# NU-Smarticles_old.net
KiCad netlist of a schematic drawn in EAGLE
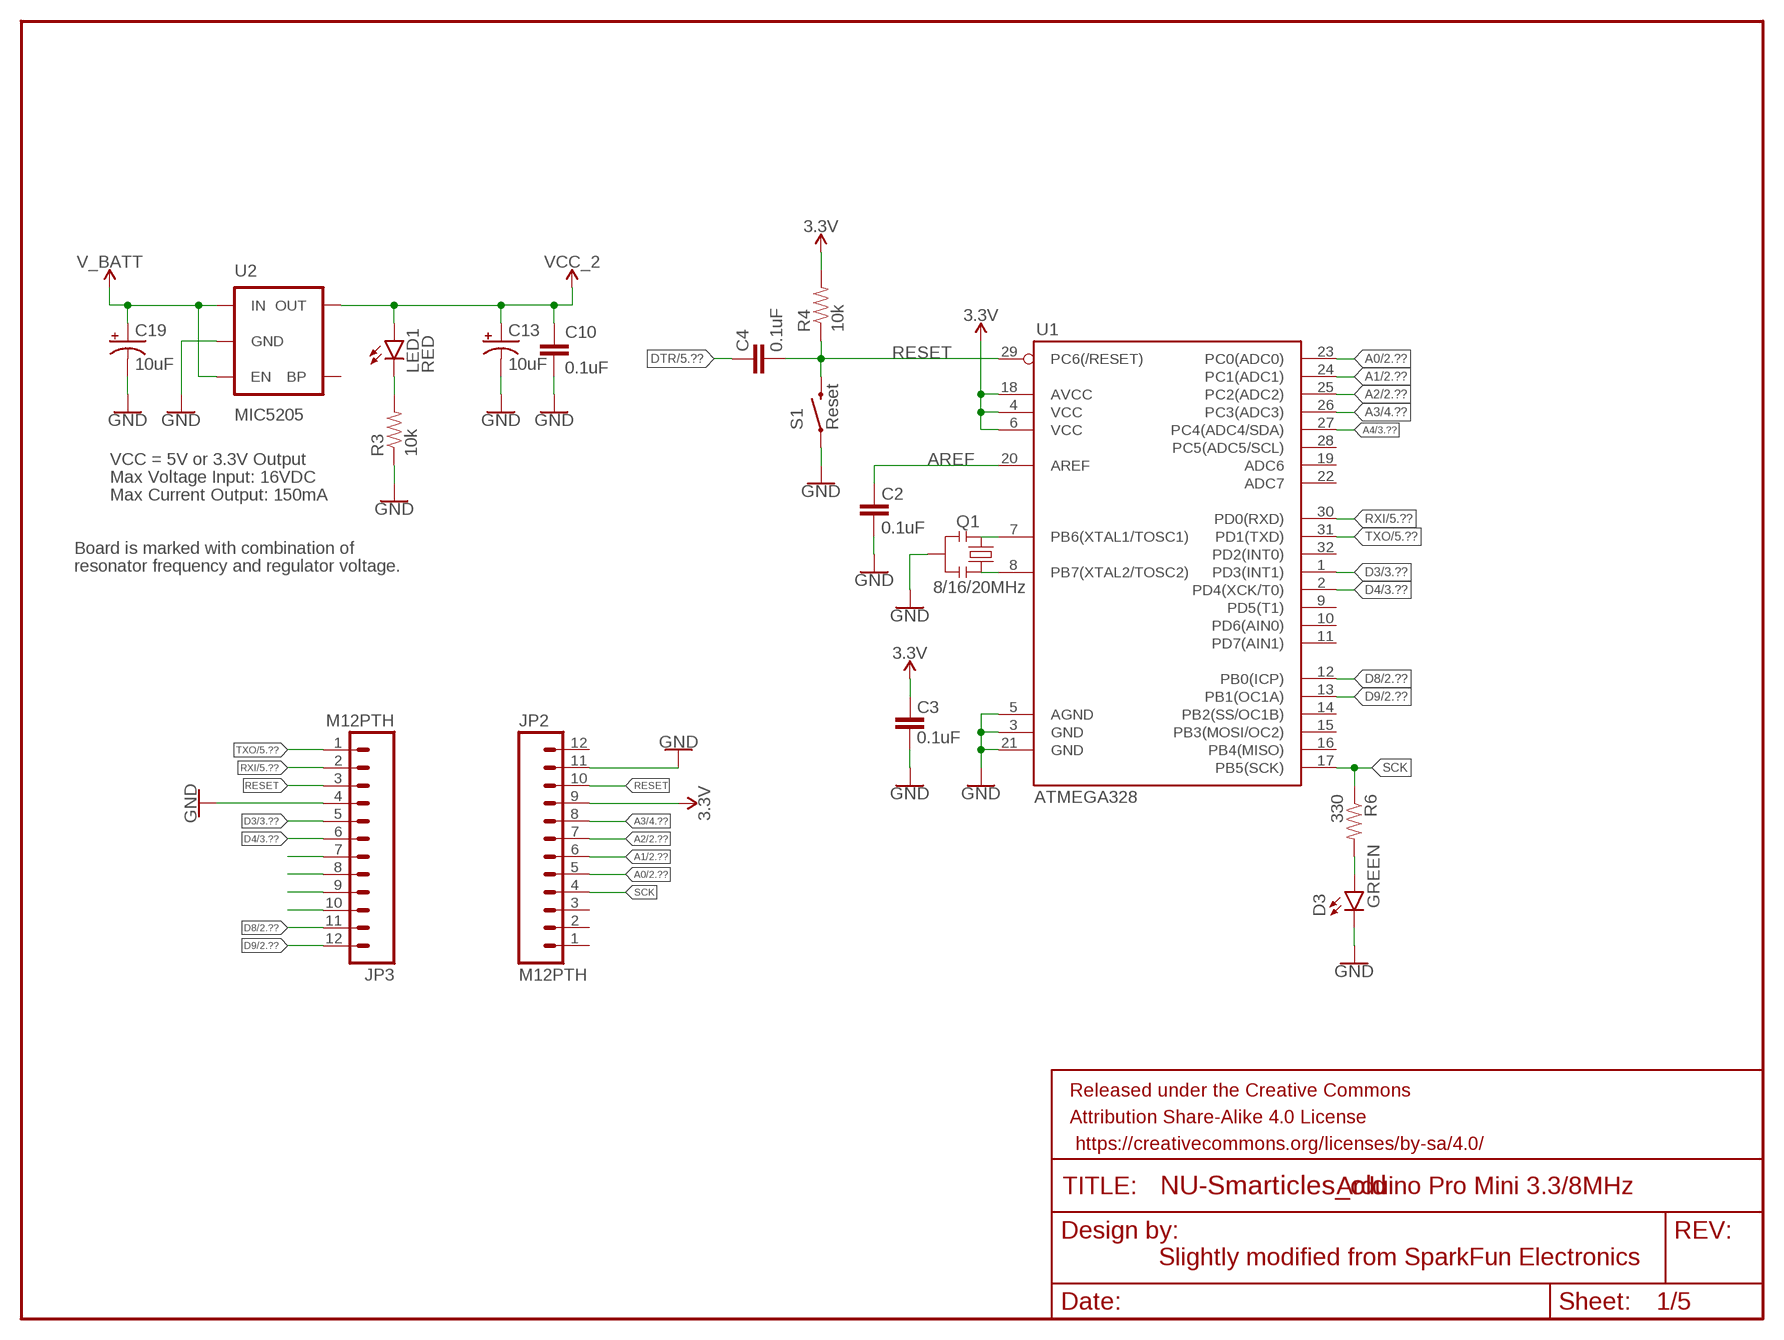
[diagram p0: schematic, sheet 1]
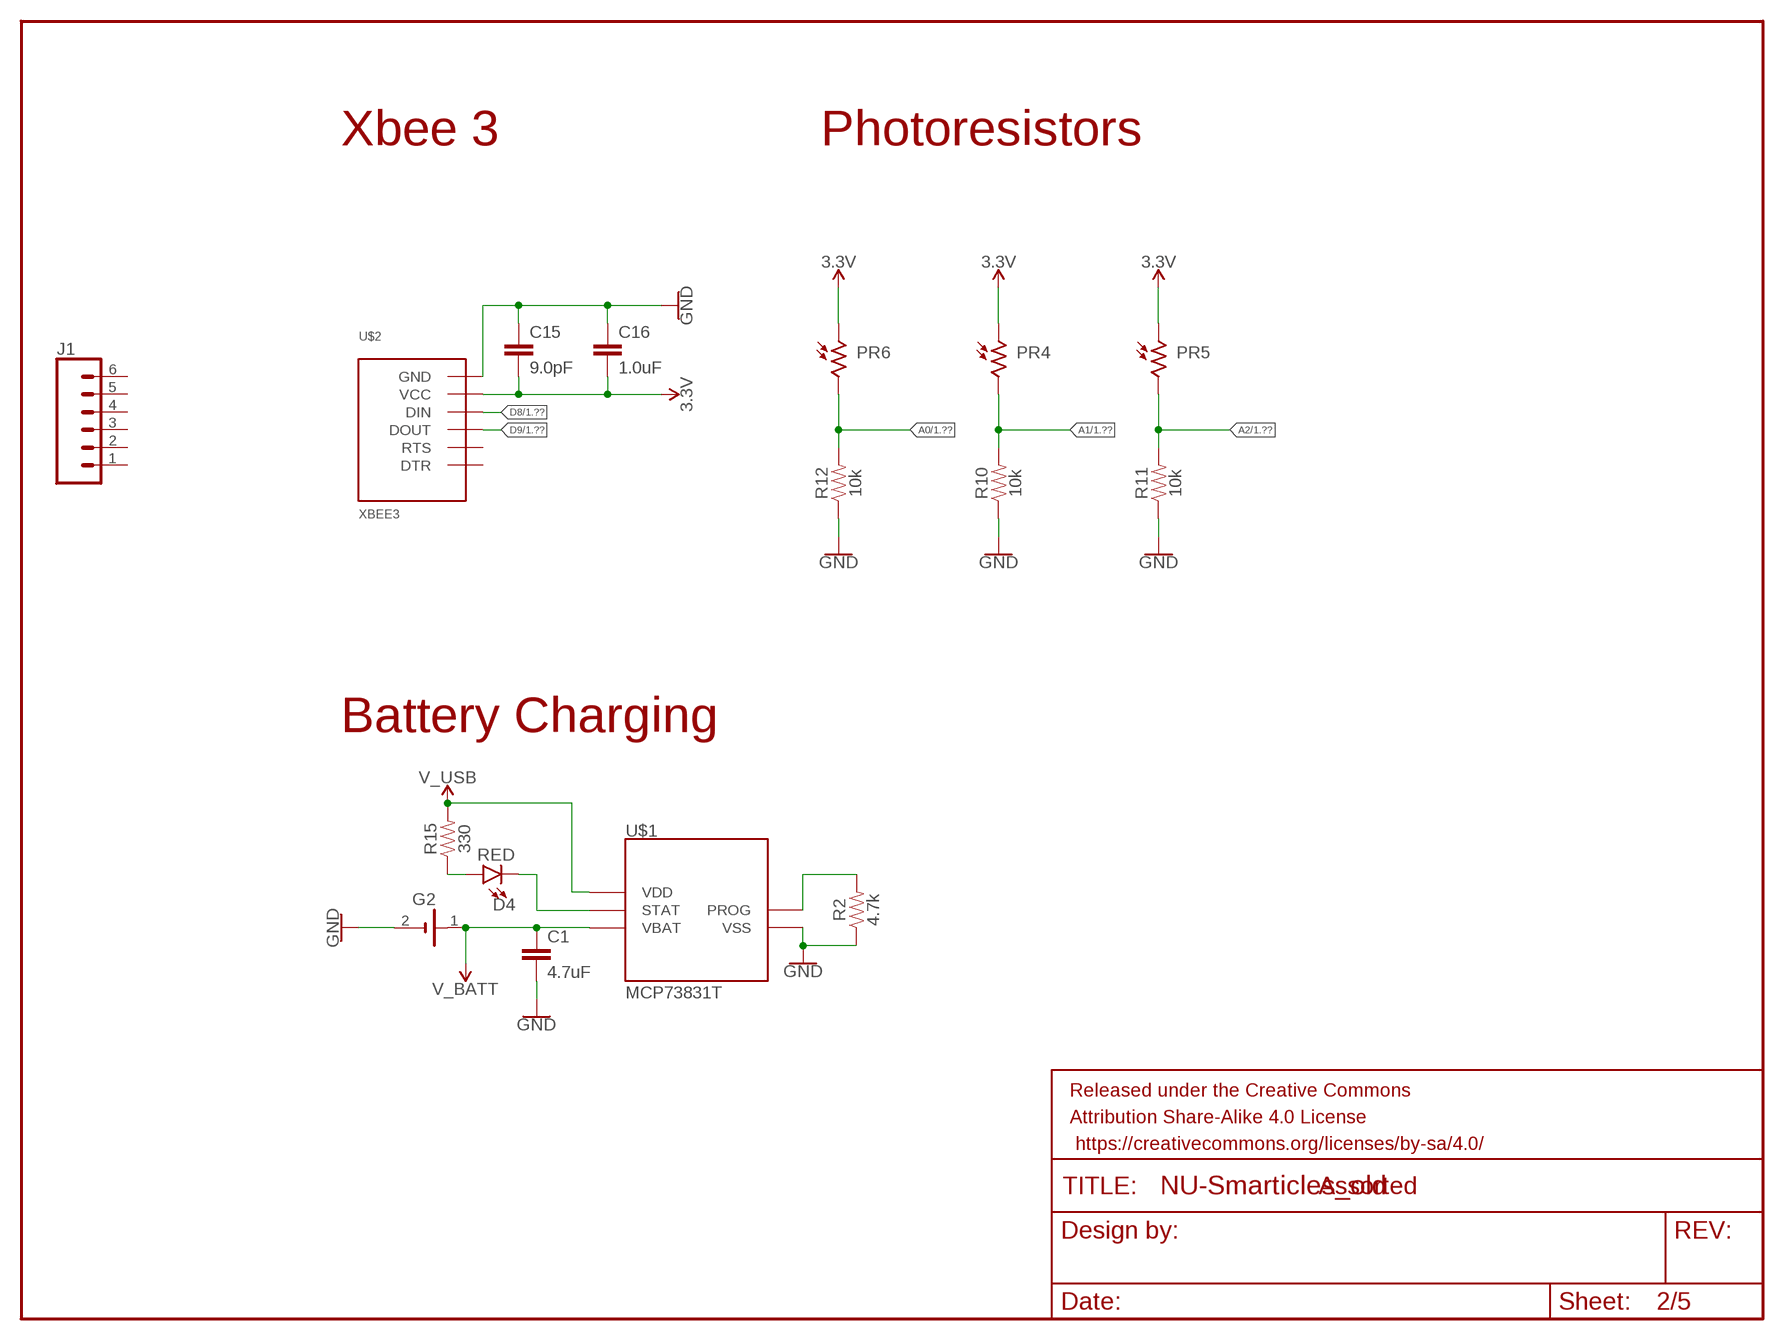
[diagram p1: schematic, sheet 2]
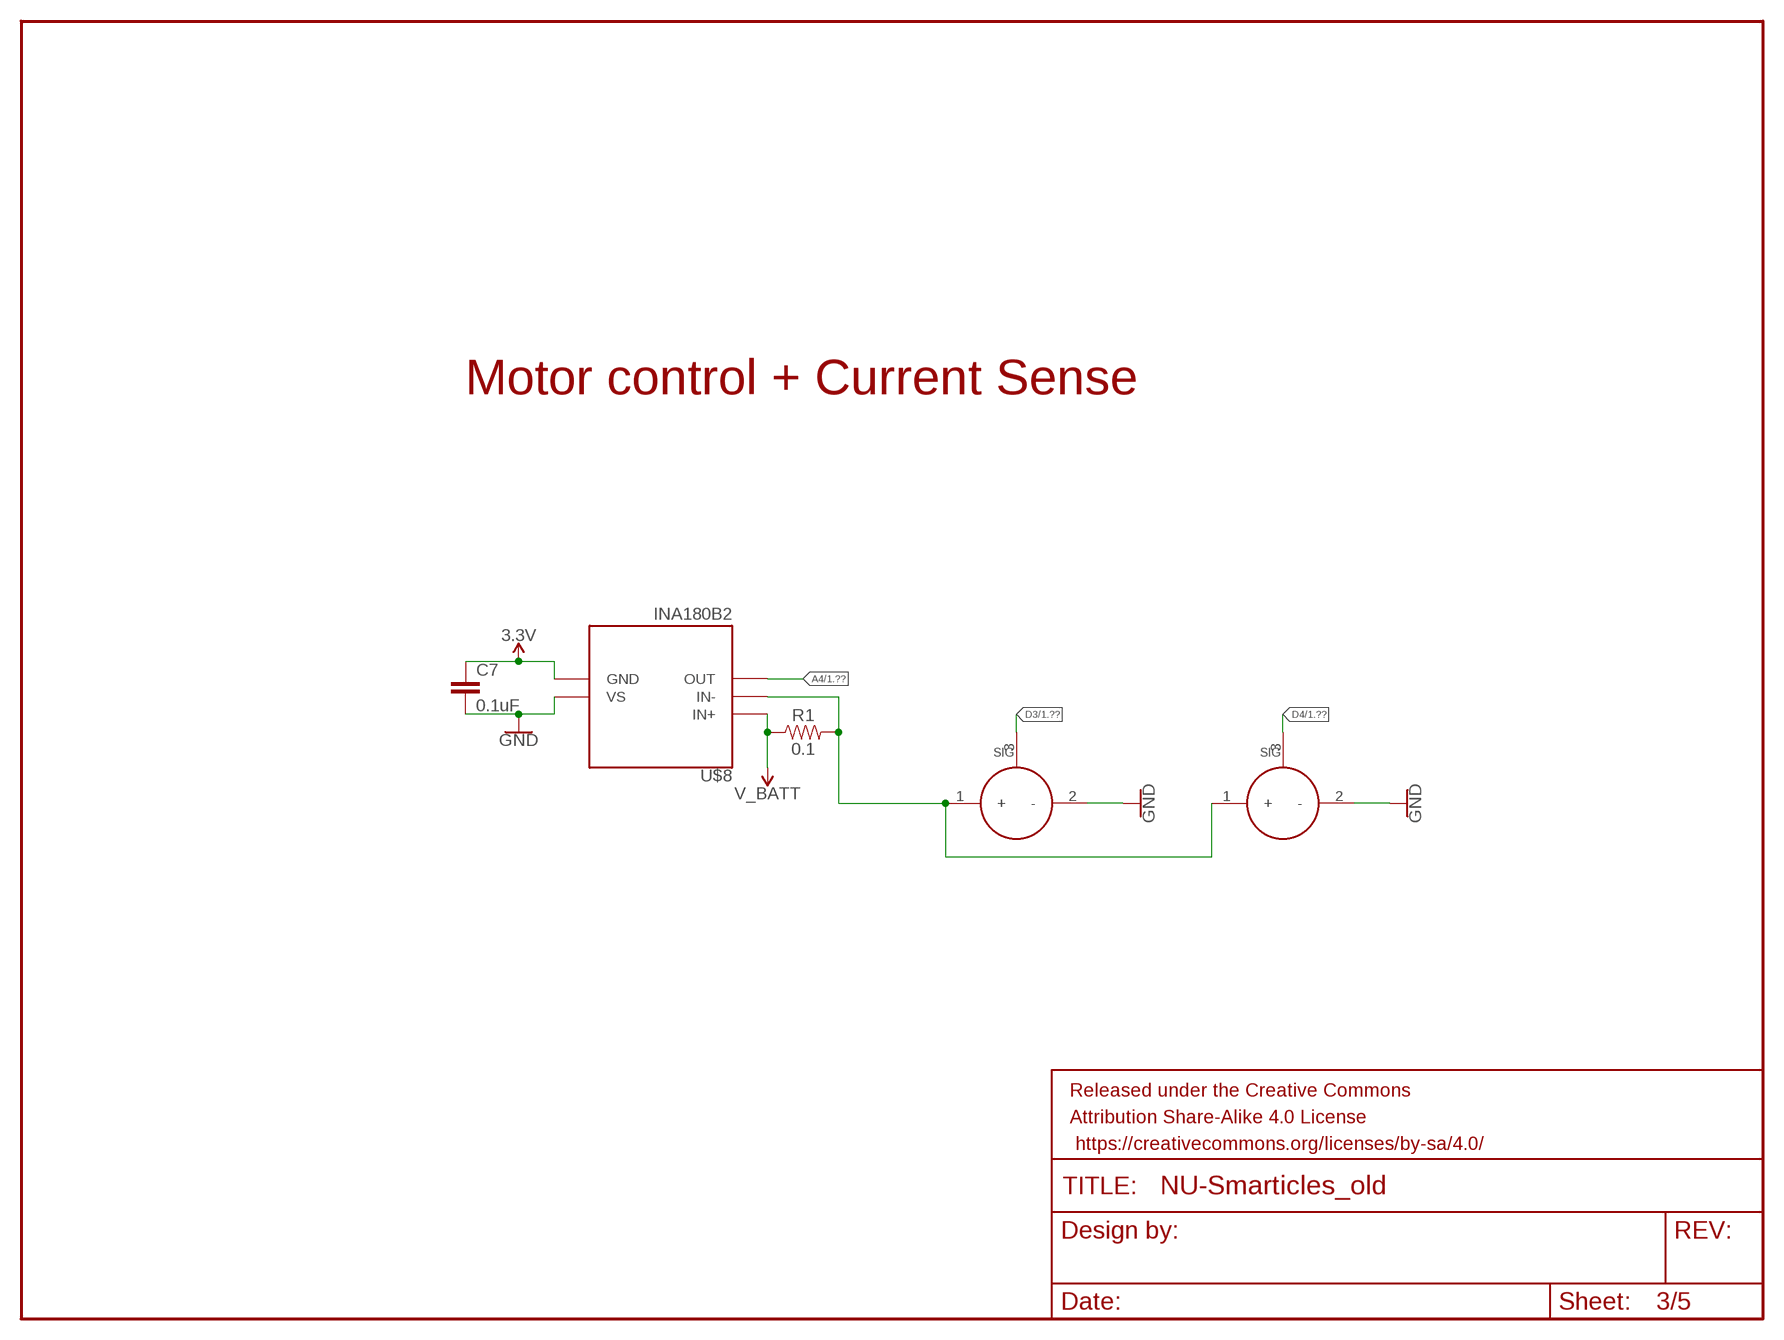
[diagram p2: schematic, sheet 3]
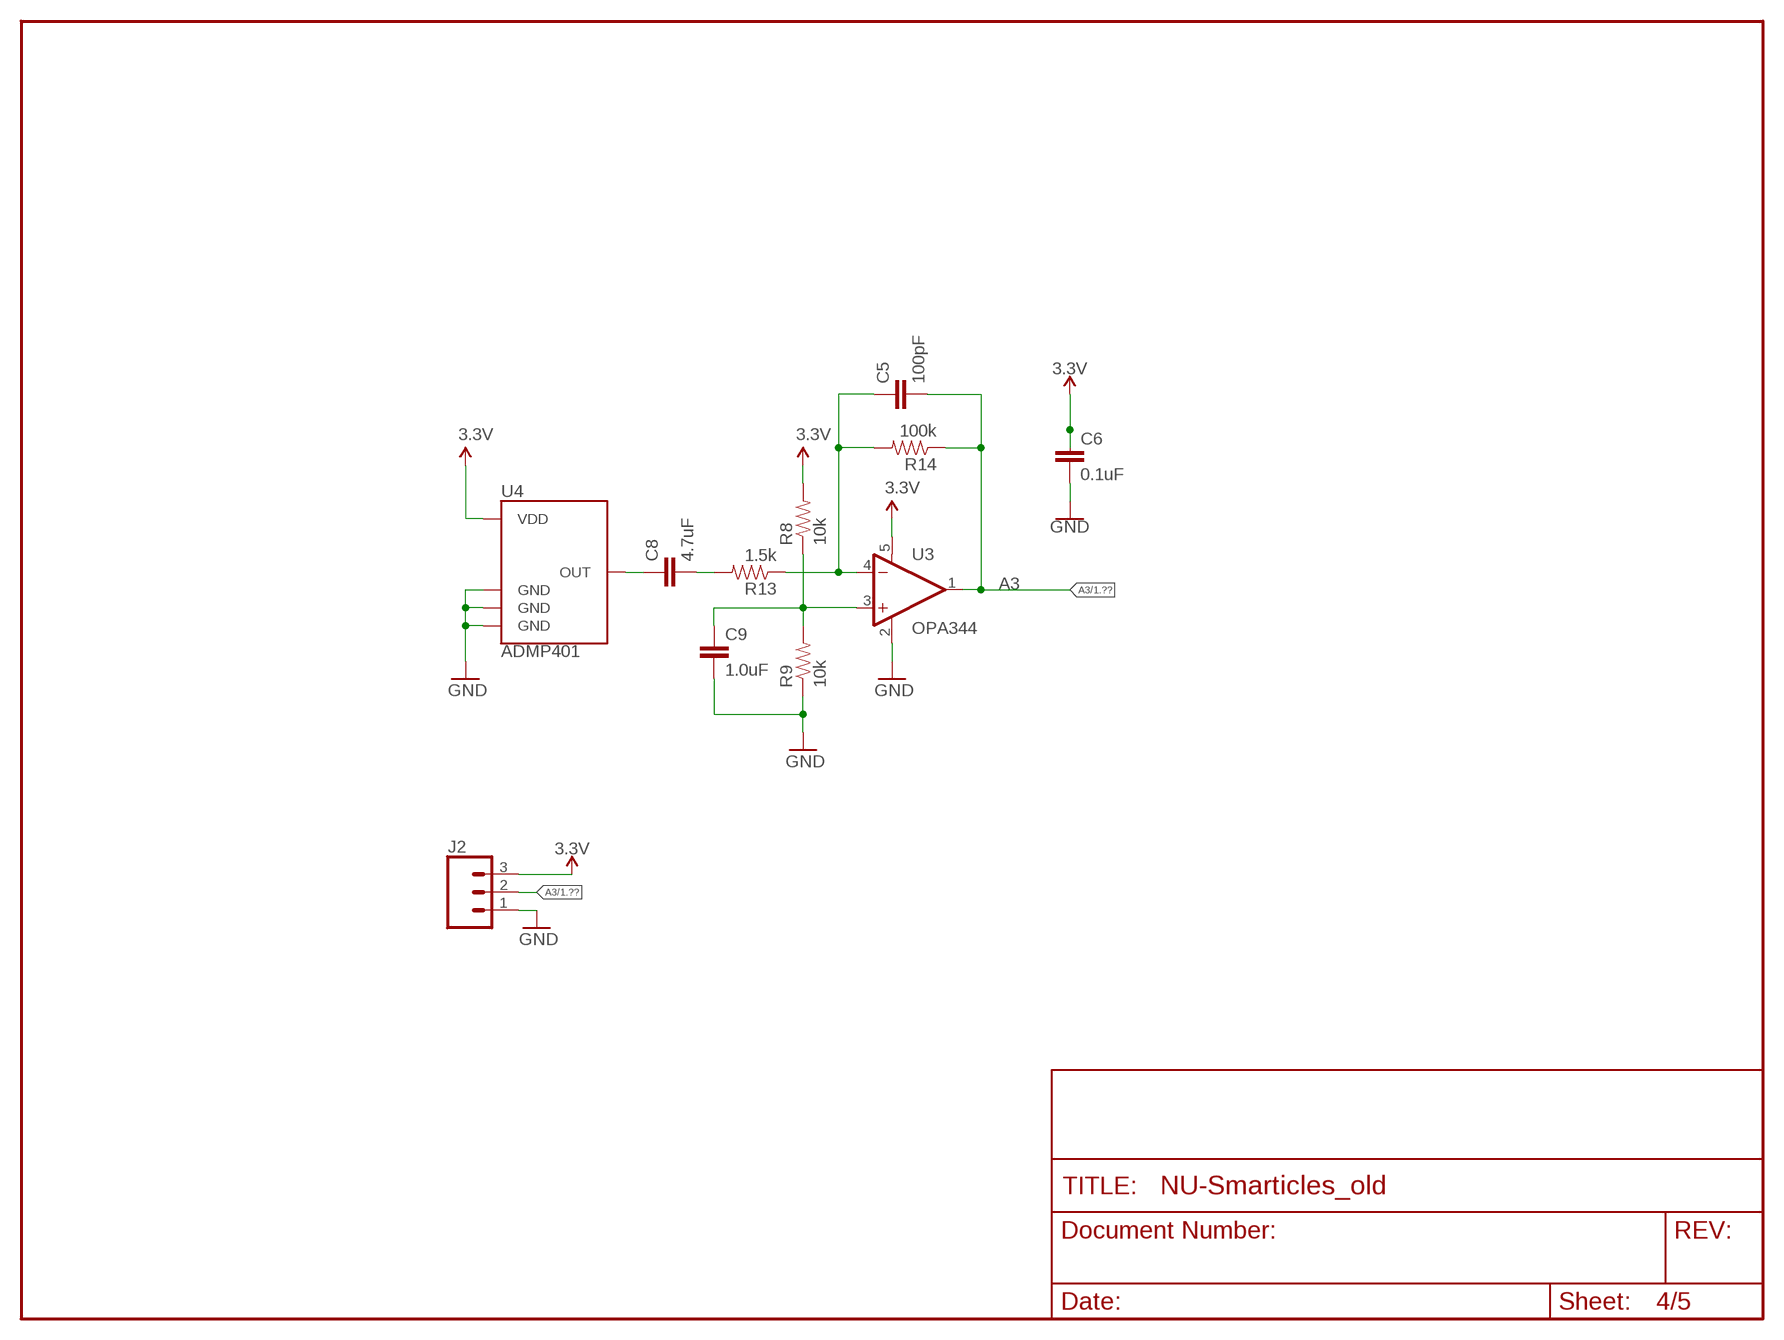
[diagram p3: schematic, sheet 4]
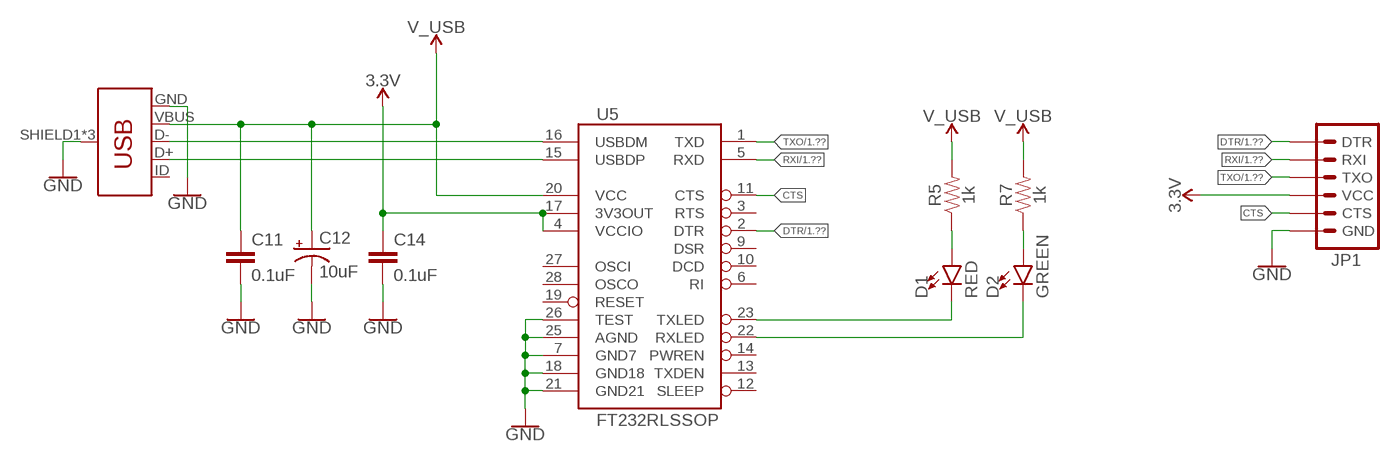
[diagram p4: schematic, sheet 5]

(export (version "E")
  (design (tool "Eeschema 10.0.6"))
  (components
    (comp (ref "C11")
      (value "0.1uF")
      (footprint "eagle-import:0603")
      (libsource (lib "eagle-import") (part "0.1UF-0603-25V-(+80/-20%)"))
    )
    (comp (ref "C12")
      (value "10uF")
      (footprint "eagle-import:0603-POLAR")
      (libsource (lib "eagle-import") (part "10UF-POLAR-0603-6.3V-20%(TANT)"))
    )
    (comp (ref "C14")
      (value "0.1uF")
      (footprint "eagle-import:0603")
      (libsource (lib "eagle-import") (part "0.1UF-0603-25V-(+80/-20%)"))
    )
    (comp (ref "D1")
      (value "RED")
      (footprint "eagle-import:LED-0603")
      (libsource (lib "eagle-import") (part "LED-RED0603"))
    )
    (comp (ref "D2")
      (value "GREEN")
      (footprint "eagle-import:LED-0603")
      (libsource (lib "eagle-import") (part "LED-GREEN0603"))
    )
    (comp (ref "JP1")
      (value "ARDUINO_SERIAL_PROGRAMPTH")
      (footprint "eagle-import:1X06")
      (libsource (lib "eagle-import") (part "ARDUINO_SERIAL_PROGRAMPTH"))
    )
    (comp (ref "R5")
      (value "1k")
      (footprint "eagle-import:0603")
      (libsource (lib "eagle-import") (part "1KOHM-0603-1/10W-1%"))
    )
    (comp (ref "R7")
      (value "1k")
      (footprint "eagle-import:0603")
      (libsource (lib "eagle-import") (part "1KOHM-0603-1/10W-1%"))
    )
    (comp (ref "U5")
      (value "FT232RLSSOP")
      (footprint "eagle-import:SSOP28DB")
      (libsource (lib "eagle-import") (part "FT232RLSSOP"))
    )
    (comp (ref "X2")
      (value "USB_MICRO-B_FEMALE-SMT")
      (footprint "eagle-import:USB-B-MICRO-SMD")
      (libsource (lib "eagle-import") (part "USB_MICRO-B_FEMALE-SMT"))
    )
    (comp (ref "C1")
      (value "4.7uF")
      (footprint "eagle-import:0603")
      (libsource (lib "eagle-import") (part "4.7UF0603"))
    )
    (comp (ref "C15")
      (value "9.0pF")
      (footprint "eagle-import:0603")
      (libsource (lib "eagle-import") (part "9.0PF-0603-50V-10%"))
    )
    (comp (ref "C16")
      (value "1.0uF")
      (footprint "eagle-import:0603")
      (libsource (lib "eagle-import") (part "1.0UF-0603-16V-10%"))
    )
    (comp (ref "D4")
      (value "RED")
      (footprint "eagle-import:LED-0603")
      (libsource (lib "eagle-import") (part "LED-RED0603"))
    )
    (comp (ref "FRAME1")
      (value "FRAME-LETTER")
      (footprint "eagle-import:CREATIVE_COMMONS")
      (libsource (lib "eagle-import") (part "SparkFun-Aesthetics_507_FRAME-LETTER"))
    )
    (comp (ref "G2")
      (value "LI-PO")
      (footprint "eagle-import:1X02_BATT")
      (libsource (lib "eagle-import") (part "LI-PO"))
    )
    (comp (ref "J1")
      (value "CONN_06NO_SILK_FEMALE_PTH")
      (footprint "eagle-import:1X06_NO_SILK")
      (libsource (lib "eagle-import") (part "CONN_06NO_SILK_FEMALE_PTH"))
    )
    (comp (ref "PR4")
      (value "A1050_09")
      (footprint "eagle-import:T0-46-A10XX")
      (libsource (lib "eagle-import") (part "A1050_09"))
    )
    (comp (ref "PR5")
      (value "A1050_09")
      (footprint "eagle-import:T0-46-A10XX")
      (libsource (lib "eagle-import") (part "A1050_09"))
    )
    (comp (ref "PR6")
      (value "A1050_09")
      (footprint "eagle-import:T0-46-A10XX")
      (libsource (lib "eagle-import") (part "A1050_09"))
    )
    (comp (ref "R2")
      (value "4.7k")
      (footprint "eagle-import:0603")
      (libsource (lib "eagle-import") (part "4.7KOHM-0603-1/10W-1%"))
    )
    (comp (ref "R10")
      (value "10k")
      (footprint "eagle-import:0603")
      (libsource (lib "eagle-import") (part "10KOHM-0603-1/10W-1%"))
    )
    (comp (ref "R11")
      (value "10k")
      (footprint "eagle-import:0603")
      (libsource (lib "eagle-import") (part "10KOHM-0603-1/10W-1%"))
    )
    (comp (ref "R12")
      (value "10k")
      (footprint "eagle-import:0603")
      (libsource (lib "eagle-import") (part "10KOHM-0603-1/10W-1%"))
    )
    (comp (ref "R15")
      (value "330")
      (footprint "eagle-import:0603")
      (libsource (lib "eagle-import") (part "330OHM-0603-1/10W-1%"))
    )
    (comp (ref "U$1")
      (value "MCP73831T")
      (footprint "eagle-import:SOT23-5")
      (libsource (lib "eagle-import") (part "MCP73831T"))
    )
    (comp (ref "U$2")
      (value "XBEE3")
      (footprint "eagle-import:XBEE3_MICRO")
      (libsource (lib "eagle-import") (part "XBEE3"))
    )
    (comp (ref "C5")
      (value "100pF")
      (footprint "eagle-import:0603")
      (libsource (lib "eagle-import") (part "100PF-0603-50V-5%"))
    )
    (comp (ref "C6")
      (value "0.1uF")
      (footprint "eagle-import:0603")
      (libsource (lib "eagle-import") (part "0.1UF-0603-25V-5%"))
    )
    (comp (ref "C8")
      (value "4.7uF")
      (footprint "eagle-import:0603")
      (libsource (lib "eagle-import") (part "4.7UF0603"))
    )
    (comp (ref "C9")
      (value "1.0uF")
      (footprint "eagle-import:0603")
      (libsource (lib "eagle-import") (part "1.0UF-0603-16V-10%"))
    )
    (comp (ref "J2")
      (value "CONN_03")
      (footprint "eagle-import:1X03")
      (libsource (lib "eagle-import") (part "CONN_03"))
    )
    (comp (ref "R8")
      (value "10k")
      (footprint "eagle-import:0603")
      (libsource (lib "eagle-import") (part "10KOHM-0603-1/10W-1%"))
    )
    (comp (ref "R9")
      (value "10k")
      (footprint "eagle-import:0603")
      (libsource (lib "eagle-import") (part "10KOHM-0603-1/10W-1%"))
    )
    (comp (ref "R13")
      (value "1.5k")
      (footprint "eagle-import:0603")
      (libsource (lib "eagle-import") (part "1.5KOHM-0603-1/10W-1%"))
    )
    (comp (ref "R14")
      (value "100k")
      (footprint "eagle-import:0603")
      (libsource (lib "eagle-import") (part "100KOHM-0603-1/10W-1%"))
    )
    (comp (ref "U3")
      (value "OPA344")
      (footprint "eagle-import:SOT23-5")
      (libsource (lib "eagle-import") (part "OPA344"))
    )
    (comp (ref "U4")
      (value "ADMP401")
      (footprint "eagle-import:ADMP401")
      (libsource (lib "eagle-import") (part "ADMP401"))
    )
    (comp (ref "C2")
      (value "0.1uF")
      (footprint "eagle-import:0603")
      (libsource (lib "eagle-import") (part "0.1UF-0603-25V-(+80/-20%)"))
    )
    (comp (ref "C3")
      (value "0.1uF")
      (footprint "eagle-import:0603")
      (libsource (lib "eagle-import") (part "0.1UF-0603-25V-(+80/-20%)"))
    )
    (comp (ref "C4")
      (value "0.1uF")
      (footprint "eagle-import:0603")
      (libsource (lib "eagle-import") (part "0.1UF-0603-25V-(+80/-20%)"))
    )
    (comp (ref "C10")
      (value "0.1uF")
      (footprint "eagle-import:0603")
      (libsource (lib "eagle-import") (part "0.1UF-0603-25V-(+80/-20%)"))
    )
    (comp (ref "C13")
      (value "10uF")
      (footprint "eagle-import:0603-POLAR")
      (libsource (lib "eagle-import") (part "10UF-POLAR-0603-6.3V-20%(TANT)"))
    )
    (comp (ref "C19")
      (value "10uF")
      (footprint "eagle-import:0603-POLAR")
      (libsource (lib "eagle-import") (part "10UF-POLAR-0603-6.3V-20%(TANT)"))
    )
    (comp (ref "D3")
      (value "GREEN")
      (footprint "eagle-import:LED-0603")
      (libsource (lib "eagle-import") (part "LED-GREEN0603"))
    )
    (comp (ref "FRAME3")
      (value "FRAME-LETTER")
      (footprint "eagle-import:CREATIVE_COMMONS")
      (libsource (lib "eagle-import") (part "SparkFun-Aesthetics_507_FRAME-LETTER"))
    )
    (comp (ref "JP2")
      (value "M12PTH")
      (footprint "eagle-import:SPARKFUN_1X12")
      (libsource (lib "eagle-import") (part "M12PTH"))
    )
    (comp (ref "JP3")
      (value "M12PTH")
      (footprint "eagle-import:SPARKFUN_1X12")
      (libsource (lib "eagle-import") (part "M12PTH"))
    )
    (comp (ref "LED1")
      (value "RED")
      (footprint "eagle-import:LED-0603")
      (libsource (lib "eagle-import") (part "LED-RED0603"))
    )
    (comp (ref "Q1")
      (value "8/16/20MHz")
      (footprint "eagle-import:TESTING_RESONATOR-SMD-1_1")
      (libsource (lib "eagle-import") (part "TESTING_RESONATOR1{colon}1"))
    )
    (comp (ref "R3")
      (value "10k")
      (footprint "eagle-import:0603")
      (libsource (lib "eagle-import") (part "10KOHM-0603-1/10W-1%"))
    )
    (comp (ref "R4")
      (value "10k")
      (footprint "eagle-import:0603")
      (libsource (lib "eagle-import") (part "10KOHM-0603-1/10W-1%"))
    )
    (comp (ref "R6")
      (value "330")
      (footprint "eagle-import:0603")
      (libsource (lib "eagle-import") (part "330OHM-0603-1/10W-1%"))
    )
    (comp (ref "S1")
      (value "Reset")
      (footprint "eagle-import:TESTING_TACTILE-SWITCH-SMD-ALT01")
      (libsource (lib "eagle-import") (part "TESTING_SWITCH-MOMENTARY-2SMD-ALT01"))
    )
    (comp (ref "U1")
      (value "ATMEGA328")
      (footprint "eagle-import:TQFP32-08")
      (libsource (lib "eagle-import") (part "ATMEGA168"))
    )
    (comp (ref "U2")
      (value "MIC5205")
      (footprint "eagle-import:SOT23-5")
      (libsource (lib "eagle-import") (part "V_REG_LDO"))
    )
    (comp (ref "C7")
      (value "0.1uF")
      (footprint "eagle-import:0603")
      (libsource (lib "eagle-import") (part "0.1UF-0603-25V-5%"))
    )
    (comp (ref "FRAME2")
      (value "FRAME-LETTER")
      (footprint "eagle-import:CREATIVE_COMMONS")
      (libsource (lib "eagle-import") (part "SparkFun-Aesthetics_507_FRAME-LETTER"))
    )
    (comp (ref "R1")
      (value "0.1")
      (footprint "eagle-import:1210")
      (libsource (lib "eagle-import") (part "0.1OHM-1210-1/2W-1%"))
    )
    (comp (ref "U$3")
      (value "SERVO")
      (footprint "eagle-import:1X03_SERVO")
      (libsource (lib "eagle-import") (part "SERVO"))
    )
    (comp (ref "U$7")
      (value "SERVO")
      (footprint "eagle-import:1X03_SERVO")
      (libsource (lib "eagle-import") (part "SERVO"))
    )
    (comp (ref "U$8")
      (value "INA180B2")
      (footprint "eagle-import:SOT23-5")
      (libsource (lib "eagle-import") (part "INA180B2"))
    )
  )
  (nets
    (net (code "1") (name "3.3V") (class "Default")
      (node (ref "C14") (pin "1") (pinfunction "1_1") (pintype "passive"))
      (node (ref "C15") (pin "2") (pinfunction "2_2") (pintype "passive"))
      (node (ref "C16") (pin "2") (pinfunction "2_2") (pintype "passive"))
      (node (ref "C3") (pin "2") (pinfunction "2_2") (pintype "passive"))
      (node (ref "C6") (pin "1") (pinfunction "1_1") (pintype "passive"))
      (node (ref "C7") (pin "1") (pinfunction "1_1") (pintype "passive"))
      (node (ref "J2") (pin "3") (pinfunction "3_3") (pintype "passive"))
      (node (ref "JP1") (pin "4") (pinfunction "VCC_4") (pintype "passive"))
      (node (ref "JP2") (pin "9") (pinfunction "9_9") (pintype "passive"))
      (node (ref "PR4") (pin "1") (pinfunction "1_1") (pintype "passive"))
      (node (ref "PR5") (pin "1") (pinfunction "1_1") (pintype "passive"))
      (node (ref "PR6") (pin "1") (pinfunction "1_1") (pintype "passive"))
      (node (ref "R4") (pin "2") (pinfunction "2_2") (pintype "passive"))
      (node (ref "R8") (pin "2") (pinfunction "2_2") (pintype "passive"))
      (node (ref "U$2") (pin "VCC") (pinfunction "VCC_VCC") (pintype "bidirectional"))
      (node (ref "U$8") (pin "2") (pinfunction "GND_2") (pintype "bidirectional"))
      (node (ref "U1") (pin "18") (pinfunction "AVCC_18") (pintype "bidirectional"))
      (node (ref "U1") (pin "4") (pinfunction "VCC_4") (pintype "bidirectional"))
      (node (ref "U1") (pin "6") (pinfunction "VCC_6") (pintype "bidirectional"))
      (node (ref "U3") (pin "5") (pinfunction "V+_5") (pintype "power_in"))
      (node (ref "U4") (pin "5") (pinfunction "VDD_5") (pintype "bidirectional"))
      (node (ref "U5") (pin "17") (pinfunction "3V3OUT_17") (pintype "output"))
      (node (ref "U5") (pin "4") (pinfunction "VCCIO_4") (pintype "power_in"))
    )
    (net (code "2") (name "A0") (class "Default")
      (node (ref "JP2") (pin "5") (pinfunction "5_5") (pintype "passive"))
      (node (ref "PR6") (pin "2") (pinfunction "2_2") (pintype "passive"))
      (node (ref "R12") (pin "2") (pinfunction "2_2") (pintype "passive"))
      (node (ref "U1") (pin "23") (pinfunction "PC0(ADC0)_23") (pintype "bidirectional"))
    )
    (net (code "3") (name "A1") (class "Default")
      (node (ref "JP2") (pin "6") (pinfunction "6_6") (pintype "passive"))
      (node (ref "PR4") (pin "2") (pinfunction "2_2") (pintype "passive"))
      (node (ref "R10") (pin "2") (pinfunction "2_2") (pintype "passive"))
      (node (ref "U1") (pin "24") (pinfunction "PC1(ADC1)_24") (pintype "bidirectional"))
    )
    (net (code "4") (name "A2") (class "Default")
      (node (ref "JP2") (pin "7") (pinfunction "7_7") (pintype "passive"))
      (node (ref "PR5") (pin "2") (pinfunction "2_2") (pintype "passive"))
      (node (ref "R11") (pin "2") (pinfunction "2_2") (pintype "passive"))
      (node (ref "U1") (pin "25") (pinfunction "PC2(ADC2)_25") (pintype "bidirectional"))
    )
    (net (code "5") (name "A3") (class "Default")
      (node (ref "C5") (pin "2") (pinfunction "2_2") (pintype "passive"))
      (node (ref "J2") (pin "2") (pinfunction "2_2") (pintype "passive"))
      (node (ref "JP2") (pin "8") (pinfunction "8_8") (pintype "passive"))
      (node (ref "R14") (pin "1") (pinfunction "1_1") (pintype "passive"))
      (node (ref "U1") (pin "26") (pinfunction "PC3(ADC3)_26") (pintype "bidirectional"))
      (node (ref "U3") (pin "1") (pinfunction "OUT_1") (pintype "output"))
    )
    (net (code "6") (name "A4") (class "Default")
      (node (ref "U$8") (pin "4") (pinfunction "OUT_4") (pintype "bidirectional"))
      (node (ref "U1") (pin "27") (pinfunction "PC4(ADC4/SDA)_27") (pintype "bidirectional"))
    )
    (net (code "7") (name "AREF") (class "Default")
      (node (ref "C2") (pin "2") (pinfunction "2_2") (pintype "passive"))
      (node (ref "U1") (pin "20") (pinfunction "AREF_20") (pintype "bidirectional"))
    )
    (net (code "8") (name "CTS") (class "Default")
      (node (ref "JP1") (pin "5") (pinfunction "CTS_5") (pintype "passive"))
      (node (ref "U5") (pin "11") (pinfunction "CTS_11") (pintype "input"))
    )
    (net (code "9") (name "D3") (class "Default")
      (node (ref "JP3") (pin "5") (pinfunction "5_5") (pintype "passive"))
      (node (ref "U$3") (pin "3") (pinfunction "SIG_3") (pintype "bidirectional"))
      (node (ref "U1") (pin "1") (pinfunction "PD3(INT1)_1") (pintype "bidirectional"))
    )
    (net (code "10") (name "D4") (class "Default")
      (node (ref "JP3") (pin "6") (pinfunction "6_6") (pintype "passive"))
      (node (ref "U$7") (pin "3") (pinfunction "SIG_3") (pintype "bidirectional"))
      (node (ref "U1") (pin "2") (pinfunction "PD4(XCK/T0)_2") (pintype "bidirectional"))
    )
    (net (code "11") (name "D8") (class "Default")
      (node (ref "JP3") (pin "11") (pinfunction "11_11") (pintype "passive"))
      (node (ref "U$2") (pin "DIN/CONFIG/DIO14") (pinfunction "DIN_DIN/CONFIG/DIO14") (pintype "bidirectional"))
      (node (ref "U1") (pin "12") (pinfunction "PB0(ICP)_12") (pintype "bidirectional"))
    )
    (net (code "12") (name "D9") (class "Default")
      (node (ref "JP3") (pin "12") (pinfunction "12_12") (pintype "passive"))
      (node (ref "U$2") (pin "DOUT/DIO13") (pinfunction "DOUT_DOUT/DIO13") (pintype "bidirectional"))
      (node (ref "U1") (pin "13") (pinfunction "PB1(OC1A)_13") (pintype "bidirectional"))
    )
    (net (code "13") (name "DTR") (class "Default")
      (node (ref "C4") (pin "2") (pinfunction "2_2") (pintype "passive"))
      (node (ref "JP1") (pin "1") (pinfunction "DTR_1") (pintype "passive"))
      (node (ref "U5") (pin "2") (pinfunction "DTR_2") (pintype "output"))
    )
    (net (code "14") (name "GND") (class "Default")
      (node (ref "C1") (pin "2") (pinfunction "2_2") (pintype "passive"))
      (node (ref "C10") (pin "2") (pinfunction "2_2") (pintype "passive"))
      (node (ref "C11") (pin "2") (pinfunction "2_2") (pintype "passive"))
      (node (ref "C12") (pin "-") (pinfunction "-_-") (pintype "passive"))
      (node (ref "C13") (pin "-") (pinfunction "-_-") (pintype "passive"))
      (node (ref "C14") (pin "2") (pinfunction "2_2") (pintype "passive"))
      (node (ref "C15") (pin "1") (pinfunction "1_1") (pintype "passive"))
      (node (ref "C16") (pin "1") (pinfunction "1_1") (pintype "passive"))
      (node (ref "C19") (pin "-") (pinfunction "-_-") (pintype "passive"))
      (node (ref "C2") (pin "1") (pinfunction "1_1") (pintype "passive"))
      (node (ref "C3") (pin "1") (pinfunction "1_1") (pintype "passive"))
      (node (ref "C6") (pin "2") (pinfunction "2_2") (pintype "passive"))
      (node (ref "C7") (pin "2") (pinfunction "2_2") (pintype "passive"))
      (node (ref "C9") (pin "2") (pinfunction "2_2") (pintype "passive"))
      (node (ref "D3") (pin "C") (pinfunction "C_C") (pintype "passive"))
      (node (ref "G2") (pin "2") (pinfunction "-_2") (pintype "passive"))
      (node (ref "J2") (pin "1") (pinfunction "1_1") (pintype "passive"))
      (node (ref "JP1") (pin "6") (pinfunction "GND_6") (pintype "passive"))
      (node (ref "JP2") (pin "11") (pinfunction "11_11") (pintype "passive"))
      (node (ref "JP3") (pin "4") (pinfunction "4_4") (pintype "passive"))
      (node (ref "Q1") (pin "2") (pinfunction "2_2") (pintype "passive"))
      (node (ref "R10") (pin "1") (pinfunction "1_1") (pintype "passive"))
      (node (ref "R11") (pin "1") (pinfunction "1_1") (pintype "passive"))
      (node (ref "R12") (pin "1") (pinfunction "1_1") (pintype "passive"))
      (node (ref "R2") (pin "1") (pinfunction "1_1") (pintype "passive"))
      (node (ref "R3") (pin "1") (pinfunction "1_1") (pintype "passive"))
      (node (ref "R9") (pin "1") (pinfunction "1_1") (pintype "passive"))
      (node (ref "S1") (pin "1") (pinfunction "1_1") (pintype "passive"))
      (node (ref "S1") (pin "2") (pinfunction "1_2") (pintype "passive"))
      (node (ref "U$1") (pin "2") (pinfunction "VSS_2") (pintype "bidirectional"))
      (node (ref "U$2") (pin "GND1") (pinfunction "GND_GND1") (pintype "bidirectional"))
      (node (ref "U$3") (pin "2") (pinfunction "-_2") (pintype "bidirectional"))
      (node (ref "U$7") (pin "2") (pinfunction "-_2") (pintype "bidirectional"))
      (node (ref "U$8") (pin "5") (pinfunction "VS_5") (pintype "bidirectional"))
      (node (ref "U1") (pin "21") (pinfunction "GND_21") (pintype "bidirectional"))
      (node (ref "U1") (pin "3") (pinfunction "GND_3") (pintype "bidirectional"))
      (node (ref "U1") (pin "5") (pinfunction "AGND_5") (pintype "bidirectional"))
      (node (ref "U2") (pin "2") (pinfunction "GND_2") (pintype "input"))
      (node (ref "U3") (pin "2") (pinfunction "V-_2") (pintype "power_in"))
      (node (ref "U4") (pin "2") (pinfunction "GND_2") (pintype "bidirectional"))
      (node (ref "U4") (pin "4") (pinfunction "GND_4") (pintype "bidirectional"))
      (node (ref "U4") (pin "6") (pinfunction "GND_6") (pintype "bidirectional"))
      (node (ref "U5") (pin "18") (pinfunction "GND18_18") (pintype "power_in"))
      (node (ref "U5") (pin "21") (pinfunction "GND21_21") (pintype "power_in"))
      (node (ref "U5") (pin "25") (pinfunction "AGND_25") (pintype "power_in"))
      (node (ref "U5") (pin "26") (pinfunction "TEST_26") (pintype "input"))
      (node (ref "U5") (pin "7") (pinfunction "GND7_7") (pintype "power_in"))
      (node (ref "X2") (pin "GND") (pinfunction "GND_GND") (pintype "bidirectional"))
      (node (ref "X2") (pin "SHIELD1") (pinfunction "SHIELD_SHIELD1") (pintype "bidirectional"))
      (node (ref "X2") (pin "SHIELD2") (pinfunction "SHIELD_SHIELD2") (pintype "bidirectional"))
      (node (ref "X2") (pin "SHIELD3") (pinfunction "SHIELD_SHIELD3") (pintype "bidirectional"))
    )
    (net (code "15") (name "ID") (class "Default")
      (node (ref "X2") (pin "ID") (pinfunction "ID_ID") (pintype "power_in"))
    )
    (net (code "16") (name "Net-(C8-Pad2)") (class "Default")
      (node (ref "C8") (pin "2") (pinfunction "2_2") (pintype "passive"))
      (node (ref "R13") (pin "2") (pinfunction "2_2") (pintype "passive"))
    )
    (net (code "17") (name "Net-(D1-PadA)") (class "Default")
      (node (ref "D1") (pin "A") (pinfunction "A_A") (pintype "passive"))
      (node (ref "R5") (pin "1") (pinfunction "1_1") (pintype "passive"))
    )
    (net (code "18") (name "Net-(D2-PadA)") (class "Default")
      (node (ref "D2") (pin "A") (pinfunction "A_A") (pintype "passive"))
      (node (ref "R7") (pin "1") (pinfunction "1_1") (pintype "passive"))
    )
    (net (code "19") (name "Net-(D3-PadA)") (class "Default")
      (node (ref "D3") (pin "A") (pinfunction "A_A") (pintype "passive"))
      (node (ref "R6") (pin "2") (pinfunction "2_2") (pintype "passive"))
    )
    (net (code "20") (name "Net-(D4-PadA)") (class "Default")
      (node (ref "D4") (pin "A") (pinfunction "A_A") (pintype "passive"))
      (node (ref "R15") (pin "1") (pinfunction "1_1") (pintype "passive"))
    )
    (net (code "21") (name "Net-(LED1-PadC)") (class "Default")
      (node (ref "LED1") (pin "C") (pinfunction "C_C") (pintype "passive"))
      (node (ref "R3") (pin "2") (pinfunction "2_2") (pintype "passive"))
    )
    (net (code "22") (name "Net-(U$1-PROG)") (class "Default")
      (node (ref "R2") (pin "2") (pinfunction "2_2") (pintype "passive"))
      (node (ref "U$1") (pin "5") (pinfunction "PROG_5") (pintype "bidirectional"))
    )
    (net (code "23") (name "Net-(U$1-STAT)") (class "Default")
      (node (ref "D4") (pin "C") (pinfunction "C_C") (pintype "passive"))
      (node (ref "U$1") (pin "1") (pinfunction "STAT_1") (pintype "bidirectional"))
    )
    (net (code "24") (name "Net-(U$3-+)") (class "Default")
      (node (ref "R1") (pin "2") (pinfunction "2_2") (pintype "passive"))
      (node (ref "U$3") (pin "1") (pinfunction "+_1") (pintype "bidirectional"))
      (node (ref "U$7") (pin "1") (pinfunction "+_1") (pintype "bidirectional"))
      (node (ref "U$8") (pin "3") (pinfunction "IN-_3") (pintype "bidirectional"))
    )
    (net (code "25") (name "Net-(U1-PB6(XTAL1{slash}TOSC1))") (class "Default")
      (node (ref "Q1") (pin "1") (pinfunction "1_1") (pintype "passive"))
      (node (ref "U1") (pin "7") (pinfunction "PB6(XTAL1/TOSC1)_7") (pintype "bidirectional"))
    )
    (net (code "26") (name "Net-(U1-PB7(XTAL2{slash}TOSC2))") (class "Default")
      (node (ref "Q1") (pin "3") (pinfunction "3_3") (pintype "passive"))
      (node (ref "U1") (pin "8") (pinfunction "PB7(XTAL2/TOSC2)_8") (pintype "bidirectional"))
    )
    (net (code "27") (name "Net-(U3-+IN)") (class "Default")
      (node (ref "C9") (pin "1") (pinfunction "1_1") (pintype "passive"))
      (node (ref "R8") (pin "1") (pinfunction "1_1") (pintype "passive"))
      (node (ref "R9") (pin "2") (pinfunction "2_2") (pintype "passive"))
      (node (ref "U3") (pin "3") (pinfunction "+IN_3") (pintype "input"))
    )
    (net (code "28") (name "Net-(U3--IN)") (class "Default")
      (node (ref "C5") (pin "1") (pinfunction "1_1") (pintype "passive"))
      (node (ref "R13") (pin "1") (pinfunction "1_1") (pintype "passive"))
      (node (ref "R14") (pin "2") (pinfunction "2_2") (pintype "passive"))
      (node (ref "U3") (pin "4") (pinfunction "-IN_4") (pintype "input"))
    )
    (net (code "29") (name "Net-(U4-OUT)") (class "Default")
      (node (ref "C8") (pin "1") (pinfunction "1_1") (pintype "passive"))
      (node (ref "U4") (pin "1") (pinfunction "OUT_1") (pintype "bidirectional"))
    )
    (net (code "30") (name "Net-(U5-RXLED)") (class "Default")
      (node (ref "D2") (pin "C") (pinfunction "C_C") (pintype "passive"))
      (node (ref "U5") (pin "22") (pinfunction "RXLED_22") (pintype "input"))
    )
    (net (code "31") (name "Net-(U5-TXLED)") (class "Default")
      (node (ref "D1") (pin "C") (pinfunction "C_C") (pintype "passive"))
      (node (ref "U5") (pin "23") (pinfunction "TXLED_23") (pintype "input"))
    )
    (net (code "32") (name "Net-(U5-USBDM)") (class "Default")
      (node (ref "U5") (pin "16") (pinfunction "USBDM_16") (pintype "bidirectional"))
      (node (ref "X2") (pin "D-") (pinfunction "D-_D-") (pintype "bidirectional"))
    )
    (net (code "33") (name "Net-(U5-USBDP)") (class "Default")
      (node (ref "U5") (pin "15") (pinfunction "USBDP_15") (pintype "bidirectional"))
      (node (ref "X2") (pin "D+") (pinfunction "D+_D+") (pintype "power_in"))
    )
    (net (code "34") (name "RESET") (class "Default")
      (node (ref "C4") (pin "1") (pinfunction "1_1") (pintype "passive"))
      (node (ref "JP2") (pin "10") (pinfunction "10_10") (pintype "passive"))
      (node (ref "JP3") (pin "3") (pinfunction "3_3") (pintype "passive"))
      (node (ref "R4") (pin "1") (pinfunction "1_1") (pintype "passive"))
      (node (ref "S1") (pin "3") (pinfunction "2_3") (pintype "passive"))
      (node (ref "S1") (pin "4") (pinfunction "2_4") (pintype "passive"))
      (node (ref "U1") (pin "29") (pinfunction "PC6(/RESET)_29") (pintype "bidirectional"))
    )
    (net (code "35") (name "RXI") (class "Default")
      (node (ref "JP1") (pin "2") (pinfunction "RXI_2") (pintype "passive"))
      (node (ref "JP3") (pin "2") (pinfunction "2_2") (pintype "passive"))
      (node (ref "U1") (pin "30") (pinfunction "PD0(RXD)_30") (pintype "bidirectional"))
      (node (ref "U5") (pin "5") (pinfunction "RXD_5") (pintype "input"))
    )
    (net (code "36") (name "SCK") (class "Default")
      (node (ref "JP2") (pin "4") (pinfunction "4_4") (pintype "passive"))
      (node (ref "R6") (pin "1") (pinfunction "1_1") (pintype "passive"))
      (node (ref "U1") (pin "17") (pinfunction "PB5(SCK)_17") (pintype "bidirectional"))
    )
    (net (code "37") (name "TXO") (class "Default")
      (node (ref "JP1") (pin "3") (pinfunction "TXO_3") (pintype "passive"))
      (node (ref "JP3") (pin "1") (pinfunction "1_1") (pintype "passive"))
      (node (ref "U1") (pin "31") (pinfunction "PD1(TXD)_31") (pintype "bidirectional"))
      (node (ref "U5") (pin "1") (pinfunction "TXD_1") (pintype "output"))
    )
    (net (code "38") (name "VCC_2") (class "Default")
      (node (ref "C10") (pin "1") (pinfunction "1_1") (pintype "passive"))
      (node (ref "C13") (pin "+") (pinfunction "+_+") (pintype "passive"))
      (node (ref "LED1") (pin "A") (pinfunction "A_A") (pintype "passive"))
      (node (ref "U2") (pin "5") (pinfunction "OUT_5") (pintype "passive"))
    )
    (net (code "39") (name "V_BATT") (class "Default")
      (node (ref "C1") (pin "1") (pinfunction "1_1") (pintype "passive"))
      (node (ref "C19") (pin "+") (pinfunction "+_+") (pintype "passive"))
      (node (ref "G2") (pin "1") (pinfunction "+_1") (pintype "passive"))
      (node (ref "R1") (pin "1") (pinfunction "1_1") (pintype "passive"))
      (node (ref "U$1") (pin "3") (pinfunction "VBAT_3") (pintype "bidirectional"))
      (node (ref "U$8") (pin "1") (pinfunction "IN+_1") (pintype "bidirectional"))
      (node (ref "U2") (pin "1") (pinfunction "IN_1") (pintype "input"))
      (node (ref "U2") (pin "3") (pinfunction "EN_3") (pintype "input"))
    )
    (net (code "40") (name "V_USB") (class "Default")
      (node (ref "C11") (pin "1") (pinfunction "1_1") (pintype "passive"))
      (node (ref "C12") (pin "+") (pinfunction "+_+") (pintype "passive"))
      (node (ref "R15") (pin "2") (pinfunction "2_2") (pintype "passive"))
      (node (ref "R5") (pin "2") (pinfunction "2_2") (pintype "passive"))
      (node (ref "R7") (pin "2") (pinfunction "2_2") (pintype "passive"))
      (node (ref "U$1") (pin "4") (pinfunction "VDD_4") (pintype "bidirectional"))
      (node (ref "U5") (pin "20") (pinfunction "VCC_20") (pintype "power_in"))
      (node (ref "X2") (pin "VBUS") (pinfunction "VBUS_VBUS") (pintype "bidirectional"))
    )
    (net (code "41") (name "unconnected-(J1-Pad1)") (class "Default")
      (node (ref "J1") (pin "1") (pinfunction "1_1") (pintype "passive"))
    )
    (net (code "42") (name "unconnected-(J1-Pad2)") (class "Default")
      (node (ref "J1") (pin "2") (pinfunction "2_2") (pintype "passive"))
    )
    (net (code "43") (name "unconnected-(J1-Pad3)") (class "Default")
      (node (ref "J1") (pin "3") (pinfunction "3_3") (pintype "passive"))
    )
    (net (code "44") (name "unconnected-(J1-Pad4)") (class "Default")
      (node (ref "J1") (pin "4") (pinfunction "4_4") (pintype "passive"))
    )
    (net (code "45") (name "unconnected-(J1-Pad5)") (class "Default")
      (node (ref "J1") (pin "5") (pinfunction "5_5") (pintype "passive"))
    )
    (net (code "46") (name "unconnected-(J1-Pad6)") (class "Default")
      (node (ref "J1") (pin "6") (pinfunction "6_6") (pintype "passive"))
    )
    (net (code "47") (name "unconnected-(JP2-Pad1)") (class "Default")
      (node (ref "JP2") (pin "1") (pinfunction "1_1") (pintype "passive"))
    )
    (net (code "48") (name "unconnected-(JP2-Pad2)") (class "Default")
      (node (ref "JP2") (pin "2") (pinfunction "2_2") (pintype "passive"))
    )
    (net (code "49") (name "unconnected-(JP2-Pad3)") (class "Default")
      (node (ref "JP2") (pin "3") (pinfunction "3_3") (pintype "passive"))
    )
    (net (code "50") (name "unconnected-(JP2-Pad12)") (class "Default")
      (node (ref "JP2") (pin "12") (pinfunction "12_12") (pintype "passive"))
    )
    (net (code "51") (name "unconnected-(JP3-Pad7)") (class "Default")
      (node (ref "JP3") (pin "7") (pinfunction "7_7") (pintype "passive"))
    )
    (net (code "52") (name "unconnected-(JP3-Pad8)") (class "Default")
      (node (ref "JP3") (pin "8") (pinfunction "8_8") (pintype "passive"))
    )
    (net (code "53") (name "unconnected-(JP3-Pad9)") (class "Default")
      (node (ref "JP3") (pin "9") (pinfunction "9_9") (pintype "passive"))
    )
    (net (code "54") (name "unconnected-(JP3-Pad10)") (class "Default")
      (node (ref "JP3") (pin "10") (pinfunction "10_10") (pintype "passive"))
    )
    (net (code "55") (name "unconnected-(U$2-DTR-PadDTR{slash}SLEEP_RQ{slash}DIO8)") (class "Default")
      (node (ref "U$2") (pin "DTR/SLEEP_RQ/DIO8") (pinfunction "DTR_DTR/SLEEP_RQ/DIO8") (pintype "bidirectional"))
    )
    (net (code "56") (name "unconnected-(U$2-RTS-PadRTS{slash}DIO6)") (class "Default")
      (node (ref "U$2") (pin "RTS/DIO6") (pinfunction "RTS_RTS/DIO6") (pintype "bidirectional"))
    )
    (net (code "57") (name "unconnected-(U1-ADC6-Pad19)") (class "Default")
      (node (ref "U1") (pin "19") (pinfunction "ADC6_19") (pintype "bidirectional"))
    )
    (net (code "58") (name "unconnected-(U1-ADC7-Pad22)") (class "Default")
      (node (ref "U1") (pin "22") (pinfunction "ADC7_22") (pintype "bidirectional"))
    )
    (net (code "59") (name "unconnected-(U1-PB2(SS{slash}OC1B)-Pad14)") (class "Default")
      (node (ref "U1") (pin "14") (pinfunction "PB2(SS/OC1B)_14") (pintype "bidirectional"))
    )
    (net (code "60") (name "unconnected-(U1-PB3(MOSI{slash}OC2)-Pad15)") (class "Default")
      (node (ref "U1") (pin "15") (pinfunction "PB3(MOSI/OC2)_15") (pintype "bidirectional"))
    )
    (net (code "61") (name "unconnected-(U1-PB4(MISO)-Pad16)") (class "Default")
      (node (ref "U1") (pin "16") (pinfunction "PB4(MISO)_16") (pintype "bidirectional"))
    )
    (net (code "62") (name "unconnected-(U1-PC5(ADC5{slash}SCL)-Pad28)") (class "Default")
      (node (ref "U1") (pin "28") (pinfunction "PC5(ADC5/SCL)_28") (pintype "bidirectional"))
    )
    (net (code "63") (name "unconnected-(U1-PD2(INT0)-Pad32)") (class "Default")
      (node (ref "U1") (pin "32") (pinfunction "PD2(INT0)_32") (pintype "bidirectional"))
    )
    (net (code "64") (name "unconnected-(U1-PD5(T1)-Pad9)") (class "Default")
      (node (ref "U1") (pin "9") (pinfunction "PD5(T1)_9") (pintype "bidirectional"))
    )
    (net (code "65") (name "unconnected-(U1-PD6(AIN0)-Pad10)") (class "Default")
      (node (ref "U1") (pin "10") (pinfunction "PD6(AIN0)_10") (pintype "bidirectional"))
    )
    (net (code "66") (name "unconnected-(U1-PD7(AIN1)-Pad11)") (class "Default")
      (node (ref "U1") (pin "11") (pinfunction "PD7(AIN1)_11") (pintype "bidirectional"))
    )
    (net (code "67") (name "unconnected-(U2-BP-Pad4)") (class "Default")
      (node (ref "U2") (pin "4") (pinfunction "BP_4") (pintype "input"))
    )
    (net (code "68") (name "unconnected-(U5-DCD-Pad10)") (class "Default")
      (node (ref "U5") (pin "10") (pinfunction "DCD_10") (pintype "input"))
    )
    (net (code "69") (name "unconnected-(U5-DSR-Pad9)") (class "Default")
      (node (ref "U5") (pin "9") (pinfunction "DSR_9") (pintype "input"))
    )
    (net (code "70") (name "unconnected-(U5-OSCI-Pad27)") (class "Default")
      (node (ref "U5") (pin "27") (pinfunction "OSCI_27") (pintype "input"))
    )
    (net (code "71") (name "unconnected-(U5-OSCO-Pad28)") (class "Default")
      (node (ref "U5") (pin "28") (pinfunction "OSCO_28") (pintype "output"))
    )
    (net (code "72") (name "unconnected-(U5-PWREN-Pad14)") (class "Default")
      (node (ref "U5") (pin "14") (pinfunction "PWREN_14") (pintype "input"))
    )
    (net (code "73") (name "unconnected-(U5-RESET-Pad19)") (class "Default")
      (node (ref "U5") (pin "19") (pinfunction "RESET_19") (pintype "input"))
    )
    (net (code "74") (name "unconnected-(U5-RI-Pad6)") (class "Default")
      (node (ref "U5") (pin "6") (pinfunction "RI_6") (pintype "input"))
    )
    (net (code "75") (name "unconnected-(U5-RTS-Pad3)") (class "Default")
      (node (ref "U5") (pin "3") (pinfunction "RTS_3") (pintype "output"))
    )
    (net (code "76") (name "unconnected-(U5-SLEEP-Pad12)") (class "Default")
      (node (ref "U5") (pin "12") (pinfunction "SLEEP_12") (pintype "input"))
    )
    (net (code "77") (name "unconnected-(U5-TXDEN-Pad13)") (class "Default")
      (node (ref "U5") (pin "13") (pinfunction "TXDEN_13") (pintype "input"))
    )
  )
)
